# eeZeeTiny43U.net
KiCad netlist of a schematic drawn in EAGLE
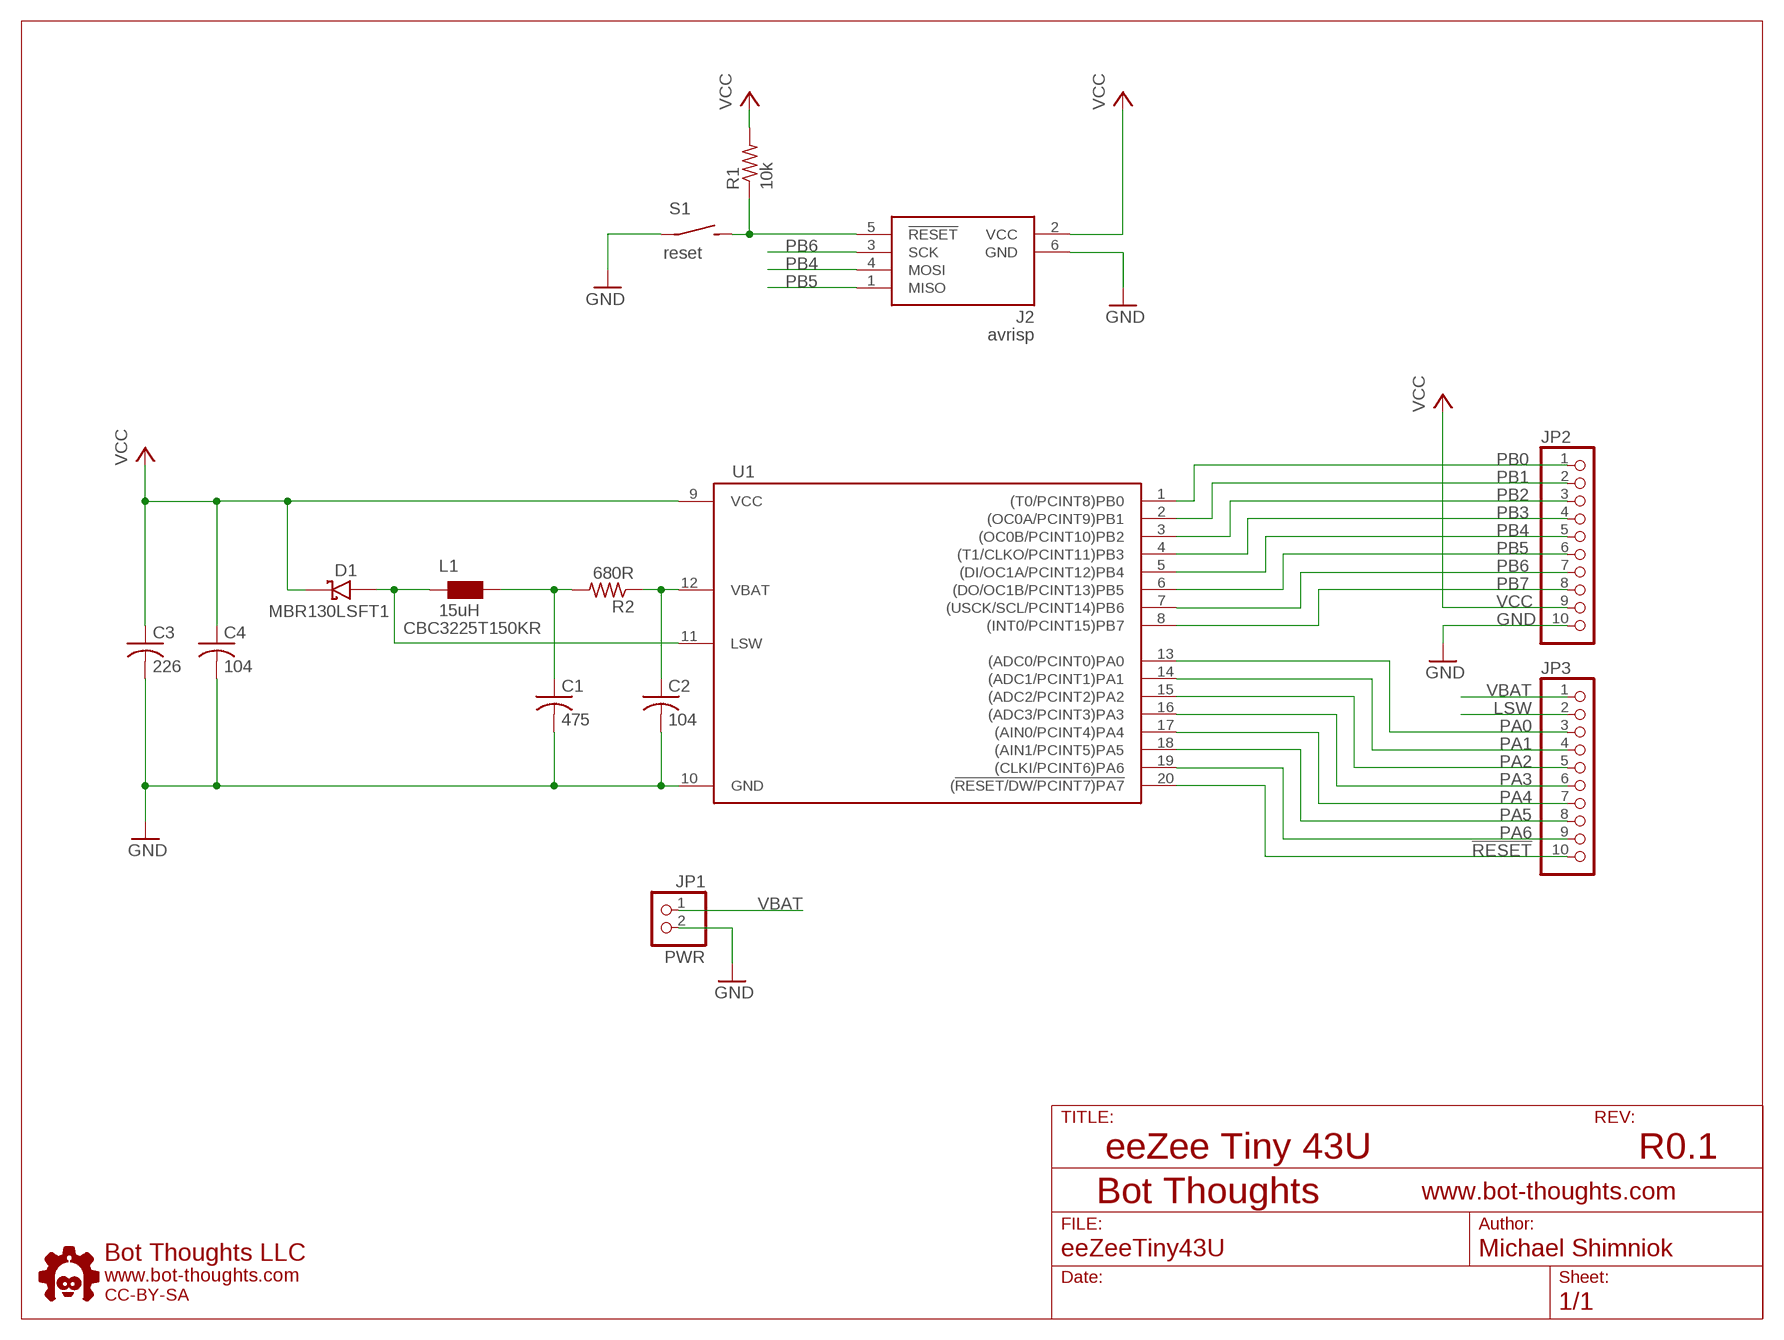
[diagram p0: schematic, sheet 1]

(export (version "E")
  (design (tool "Eeschema 10.0.6"))
  (components
    (comp (ref "C1")
      (value "475")
      (footprint "eagle-import:0603")
      (fields (field (name "PARTNO") "0603YC104KAT2A"))
      (libsource (lib "eagle-import") (part "C-0603"))
    )
    (comp (ref "C2")
      (value "104")
      (footprint "eagle-import:0603")
      (fields (field (name "PARTNO") "0603YC104KAT2A"))
      (libsource (lib "eagle-import") (part "C-0603"))
    )
    (comp (ref "C3")
      (value "226")
      (footprint "eagle-import:1206")
      (fields (field (name "PARTNO") "MCTT21X106M6R3CT"))
      (libsource (lib "eagle-import") (part "C-1206"))
    )
    (comp (ref "C4")
      (value "104")
      (footprint "eagle-import:0603")
      (fields (field (name "PARTNO") "0603YC104KAT2A"))
      (libsource (lib "eagle-import") (part "C-0603"))
    )
    (comp (ref "D1")
      (value "MBR130LSFT1")
      (footprint "eagle-import:SOD123FL")
      (libsource (lib "eagle-import") (part "SCHOTTKY-DIODE-MBR130LSFT1"))
    )
    (comp (ref "J2")
      (value "avrisp")
      (footprint "eagle-import:CON6P2R")
      (libsource (lib "eagle-import") (part "AVRISP6_COMPACT"))
    )
    (comp (ref "JP1")
      (value "PWR")
      (footprint "eagle-import:1X02-S")
      (libsource (lib "eagle-import") (part "PINHD-1X02_2.54-S"))
    )
    (comp (ref "JP2")
      (value "PINHD-1X10_2.54-S")
      (footprint "eagle-import:1X10-S")
      (libsource (lib "eagle-import") (part "PINHD-1X10_2.54-S"))
    )
    (comp (ref "JP3")
      (value "PINHD-1X10_2.54-S")
      (footprint "eagle-import:1X10-S")
      (libsource (lib "eagle-import") (part "PINHD-1X10_2.54-S"))
    )
    (comp (ref "L1")
      (value "15uH")
      (footprint "eagle-import:1210")
      (fields (field (name "PARTNO") "CBC3225T150KR"))
      (libsource (lib "eagle-import") (part "WE-CBF_1210"))
    )
    (comp (ref "R1")
      (value "10k")
      (footprint "eagle-import:0603")
      (fields (field (name "PARTNO") "ERJ-3GEYJ103V"))
      (libsource (lib "eagle-import") (part "R0603"))
    )
    (comp (ref "R2")
      (value "680R")
      (footprint "eagle-import:0603")
      (fields (field (name "PARTNO") "ERJ-3GEYJ103V"))
      (libsource (lib "eagle-import") (part "R0603"))
    )
    (comp (ref "S1")
      (value "reset")
      (footprint "eagle-import:6MMTACTILE_RECT")
      (libsource (lib "eagle-import") (part "SPST_TAC_RECT1"))
    )
    (comp (ref "U$1")
      (value "BTLOGO-LOGO-MD")
      (footprint "eagle-import:BTLOGOM")
      (libsource (lib "eagle-import") (part "BTLOGO-LOGO-MD"))
    )
    (comp (ref "U1")
      (value "ATTINY43U-SU")
      (footprint "eagle-import:SOIC20")
      (libsource (lib "eagle-import") (part "ATTINY43U-SU"))
    )
  )
  (nets
    (net (code "1") (name "/LSW") (class "Default")
      (node (ref "D1") (pin "A") (pinfunction "A_A") (pintype "passive"))
      (node (ref "JP3") (pin "2") (pinfunction "2_2") (pintype "passive"))
      (node (ref "L1") (pin "1") (pinfunction "1_1") (pintype "passive"))
      (node (ref "U1") (pin "11") (pinfunction "LSW_11") (pintype "bidirectional"))
    )
    (net (code "2") (name "/PA0") (class "Default")
      (node (ref "JP3") (pin "3") (pinfunction "3_3") (pintype "passive"))
      (node (ref "U1") (pin "13") (pinfunction "(ADC0/PCINT0)PA0_13") (pintype "bidirectional"))
    )
    (net (code "3") (name "/PA1") (class "Default")
      (node (ref "JP3") (pin "4") (pinfunction "4_4") (pintype "passive"))
      (node (ref "U1") (pin "14") (pinfunction "(ADC1/PCINT1)PA1_14") (pintype "bidirectional"))
    )
    (net (code "4") (name "/PA2") (class "Default")
      (node (ref "JP3") (pin "5") (pinfunction "5_5") (pintype "passive"))
      (node (ref "U1") (pin "15") (pinfunction "(ADC2/PCINT2)PA2_15") (pintype "bidirectional"))
    )
    (net (code "5") (name "/PA3") (class "Default")
      (node (ref "JP3") (pin "6") (pinfunction "6_6") (pintype "passive"))
      (node (ref "U1") (pin "16") (pinfunction "(ADC3/PCINT3)PA3_16") (pintype "bidirectional"))
    )
    (net (code "6") (name "/PA4") (class "Default")
      (node (ref "JP3") (pin "7") (pinfunction "7_7") (pintype "passive"))
      (node (ref "U1") (pin "17") (pinfunction "(AIN0/PCINT4)PA4_17") (pintype "bidirectional"))
    )
    (net (code "7") (name "/PA5") (class "Default")
      (node (ref "JP3") (pin "8") (pinfunction "8_8") (pintype "passive"))
      (node (ref "U1") (pin "18") (pinfunction "(AIN1/PCINT5)PA5_18") (pintype "bidirectional"))
    )
    (net (code "8") (name "/PA6") (class "Default")
      (node (ref "JP3") (pin "9") (pinfunction "9_9") (pintype "passive"))
      (node (ref "U1") (pin "19") (pinfunction "(CLKI/PCINT6)PA6_19") (pintype "bidirectional"))
    )
    (net (code "9") (name "/PB0") (class "Default")
      (node (ref "JP2") (pin "1") (pinfunction "1_1") (pintype "passive"))
      (node (ref "U1") (pin "1") (pinfunction "(T0/PCINT8)PB0_1") (pintype "bidirectional"))
    )
    (net (code "10") (name "/PB1") (class "Default")
      (node (ref "JP2") (pin "2") (pinfunction "2_2") (pintype "passive"))
      (node (ref "U1") (pin "2") (pinfunction "(OC0A/PCINT9)PB1_2") (pintype "bidirectional"))
    )
    (net (code "11") (name "/PB2") (class "Default")
      (node (ref "JP2") (pin "3") (pinfunction "3_3") (pintype "passive"))
      (node (ref "U1") (pin "3") (pinfunction "(OC0B/PCINT10)PB2_3") (pintype "bidirectional"))
    )
    (net (code "12") (name "/PB3") (class "Default")
      (node (ref "JP2") (pin "4") (pinfunction "4_4") (pintype "passive"))
      (node (ref "U1") (pin "4") (pinfunction "(T1/CLKO/PCINT11)PB3_4") (pintype "bidirectional"))
    )
    (net (code "13") (name "/PB4") (class "Default")
      (node (ref "J2") (pin "4") (pinfunction "MOSI_4") (pintype "output"))
      (node (ref "JP2") (pin "5") (pinfunction "5_5") (pintype "passive"))
      (node (ref "U1") (pin "5") (pinfunction "(DI/OC1A/PCINT12)PB4_5") (pintype "bidirectional"))
    )
    (net (code "14") (name "/PB5") (class "Default")
      (node (ref "J2") (pin "1") (pinfunction "MISO_1") (pintype "input"))
      (node (ref "JP2") (pin "6") (pinfunction "6_6") (pintype "passive"))
      (node (ref "U1") (pin "6") (pinfunction "(DO/OC1B/PCINT13)PB5_6") (pintype "bidirectional"))
    )
    (net (code "15") (name "/PB6") (class "Default")
      (node (ref "J2") (pin "3") (pinfunction "SCK_3") (pintype "output"))
      (node (ref "JP2") (pin "7") (pinfunction "7_7") (pintype "passive"))
      (node (ref "U1") (pin "7") (pinfunction "(USCK/SCL/PCINT14)PB6_7") (pintype "bidirectional"))
    )
    (net (code "16") (name "/PB7") (class "Default")
      (node (ref "JP2") (pin "8") (pinfunction "8_8") (pintype "passive"))
      (node (ref "U1") (pin "8") (pinfunction "(INT0/PCINT15)PB7_8") (pintype "bidirectional"))
    )
    (net (code "17") (name "/VBAT") (class "Default")
      (node (ref "C2") (pin "1") (pinfunction "+_1") (pintype "passive"))
      (node (ref "JP1") (pin "1") (pinfunction "1_1") (pintype "passive"))
      (node (ref "JP3") (pin "1") (pinfunction "1_1") (pintype "passive"))
      (node (ref "R2") (pin "1") (pinfunction "1_1") (pintype "passive"))
      (node (ref "U1") (pin "12") (pinfunction "VBAT_12") (pintype "bidirectional"))
    )
    (net (code "18") (name "/~{RESET}") (class "Default")
      (node (ref "J2") (pin "5") (pinfunction "~{RESET}_5") (pintype "output"))
      (node (ref "JP3") (pin "10") (pinfunction "10_10") (pintype "passive"))
      (node (ref "R1") (pin "1") (pinfunction "1_1") (pintype "passive"))
      (node (ref "S1") (pin "P$2") (pinfunction "S_P$2") (pintype "passive"))
      (node (ref "U1") (pin "20") (pinfunction "(~{RESET/DW/PCINT7})PA7_20") (pintype "bidirectional"))
    )
    (net (code "19") (name "GND") (class "Default")
      (node (ref "C1") (pin "2") (pinfunction "-_2") (pintype "passive"))
      (node (ref "C2") (pin "2") (pinfunction "-_2") (pintype "passive"))
      (node (ref "C3") (pin "2") (pinfunction "-_2") (pintype "passive"))
      (node (ref "C4") (pin "2") (pinfunction "-_2") (pintype "passive"))
      (node (ref "J2") (pin "6") (pinfunction "GND_6") (pintype "power_in"))
      (node (ref "JP1") (pin "2") (pinfunction "2_2") (pintype "passive"))
      (node (ref "JP2") (pin "10") (pinfunction "10_10") (pintype "passive"))
      (node (ref "S1") (pin "P$1") (pinfunction "P_P$1") (pintype "passive"))
      (node (ref "U1") (pin "10") (pinfunction "GND_10") (pintype "bidirectional"))
    )
    (net (code "20") (name "Net-(C1-+)") (class "Default")
      (node (ref "C1") (pin "1") (pinfunction "+_1") (pintype "passive"))
      (node (ref "L1") (pin "2") (pinfunction "2_2") (pintype "passive"))
      (node (ref "R2") (pin "2") (pinfunction "2_2") (pintype "passive"))
    )
    (net (code "21") (name "VCC") (class "Default")
      (node (ref "C3") (pin "1") (pinfunction "+_1") (pintype "passive"))
      (node (ref "C4") (pin "1") (pinfunction "+_1") (pintype "passive"))
      (node (ref "D1") (pin "C") (pinfunction "C_C") (pintype "passive"))
      (node (ref "J2") (pin "2") (pinfunction "VCC_2") (pintype "power_in"))
      (node (ref "JP2") (pin "9") (pinfunction "9_9") (pintype "passive"))
      (node (ref "R1") (pin "2") (pinfunction "2_2") (pintype "passive"))
      (node (ref "U1") (pin "9") (pinfunction "VCC_9") (pintype "bidirectional"))
    )
  )
)
